# RTD_interface.net
KiCad netlist of a schematic drawn in Altium Designer
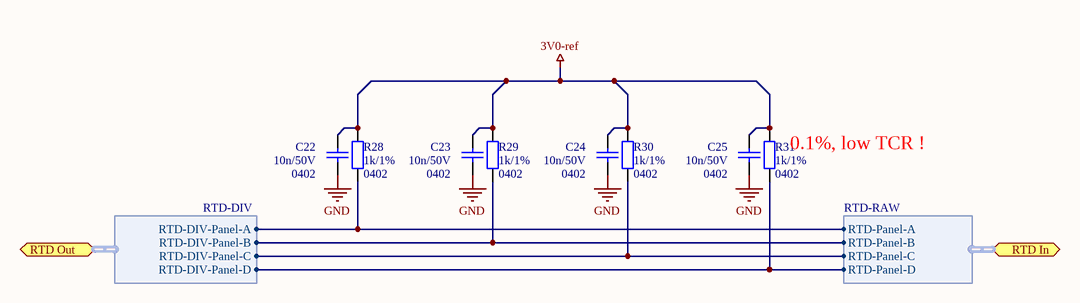
[diagram p0: RTD_interface.SchDoc]

(export (version "E")
  (design (tool "Eeschema 10.0.6"))
  (components
    (comp (ref "C22")
      (value "10n/50V")
      (footprint "SMD_Capacitor_0402")
      (description "Ceramic Cap Kemet COTS 10n/50V X7R 0402")
      (fields
        (field (name "MANUFACTURERPARTNUMBER") "C0402T103K5RALTU")
        (field (name "MANUFACTURER") "Kemet")
        (field (name "PACKAGE") "0402")
      )
      (libsource (lib "capacitors") (part "Cer_C0402T103K5RALTU"))
    )
    (comp (ref "C23")
      (value "10n/50V")
      (footprint "SMD_Capacitor_0402")
      (description "Ceramic Cap Kemet COTS 10n/50V X7R 0402")
      (fields
        (field (name "MANUFACTURERPARTNUMBER") "C0402T103K5RALTU")
        (field (name "MANUFACTURER") "Kemet")
        (field (name "PACKAGE") "0402")
      )
      (libsource (lib "capacitors") (part "Cer_C0402T103K5RALTU"))
    )
    (comp (ref "C24")
      (value "10n/50V")
      (footprint "SMD_Capacitor_0402")
      (description "Ceramic Cap Kemet COTS 10n/50V X7R 0402")
      (fields
        (field (name "MANUFACTURERPARTNUMBER") "C0402T103K5RALTU")
        (field (name "MANUFACTURER") "Kemet")
        (field (name "PACKAGE") "0402")
      )
      (libsource (lib "capacitors") (part "Cer_C0402T103K5RALTU"))
    )
    (comp (ref "C25")
      (value "10n/50V")
      (footprint "SMD_Capacitor_0402")
      (description "Ceramic Cap Kemet COTS 10n/50V X7R 0402")
      (fields
        (field (name "MANUFACTURERPARTNUMBER") "C0402T103K5RALTU")
        (field (name "MANUFACTURER") "Kemet")
        (field (name "PACKAGE") "0402")
      )
      (libsource (lib "capacitors") (part "Cer_C0402T103K5RALTU"))
    )
    (comp (ref "R28")
      (value "1k/1%")
      (footprint "SMD_Resistor_0402")
      (description "1k/1% Vishay CRCW 0402 Resistor. 63mW, 100ppm, 50V.")
      (fields
        (field (name "MANUFACTURER") "Vishay")
        (field (name "MANUFACTURERPARTNUMBER") "CRCW04021K00FKxxxx")
        (field (name "PACKAGE") "0402")
      )
      (libsource (lib "resistors") (part "CRCW04021K00FKxxxx"))
    )
    (comp (ref "R29")
      (value "1k/1%")
      (footprint "SMD_Resistor_0402")
      (description "1k/1% Vishay CRCW 0402 Resistor. 63mW, 100ppm, 50V.")
      (fields
        (field (name "MANUFACTURER") "Vishay")
        (field (name "MANUFACTURERPARTNUMBER") "CRCW04021K00FKxxxx")
        (field (name "PACKAGE") "0402")
      )
      (libsource (lib "resistors") (part "CRCW04021K00FKxxxx"))
    )
    (comp (ref "R30")
      (value "1k/1%")
      (footprint "SMD_Resistor_0402")
      (description "1k/1% Vishay CRCW 0402 Resistor. 63mW, 100ppm, 50V.")
      (fields
        (field (name "MANUFACTURER") "Vishay")
        (field (name "MANUFACTURERPARTNUMBER") "CRCW04021K00FKxxxx")
        (field (name "PACKAGE") "0402")
      )
      (libsource (lib "resistors") (part "CRCW04021K00FKxxxx"))
    )
    (comp (ref "R31")
      (value "1k/1%")
      (footprint "SMD_Resistor_0402")
      (description "1k/1% Vishay CRCW 0402 Resistor. 63mW, 100ppm, 50V.")
      (fields
        (field (name "MANUFACTURER") "Vishay")
        (field (name "MANUFACTURERPARTNUMBER") "CRCW04021K00FKxxxx")
        (field (name "PACKAGE") "0402")
      )
      (libsource (lib "resistors") (part "CRCW04021K00FKxxxx"))
    )
  )
  (nets
    (net (code "3") (name "/RTD-DIV-Panel-A") (class "Default")
      (node (ref "R28") (pin "2") (pinfunction "2_2") (pintype "passive"))
    )
    (net (code "4") (name "/RTD-DIV-Panel-B") (class "Default")
      (node (ref "R29") (pin "2") (pinfunction "2_2") (pintype "passive"))
    )
    (net (code "5") (name "/RTD-DIV-Panel-C") (class "Default")
      (node (ref "R30") (pin "2") (pinfunction "2_2") (pintype "passive"))
    )
    (net (code "6") (name "/RTD-DIV-Panel-D") (class "Default")
      (node (ref "R31") (pin "2") (pinfunction "2_2") (pintype "passive"))
    )
    (net (code "9") (name "3V0-ref") (class "Default")
      (node (ref "C22") (pin "1") (pinfunction "1_1") (pintype "passive"))
      (node (ref "C23") (pin "1") (pinfunction "1_1") (pintype "passive"))
      (node (ref "C24") (pin "1") (pinfunction "1_1") (pintype "passive"))
      (node (ref "C25") (pin "1") (pinfunction "1_1") (pintype "passive"))
      (node (ref "R28") (pin "1") (pinfunction "1_1") (pintype "passive"))
      (node (ref "R29") (pin "1") (pinfunction "1_1") (pintype "passive"))
      (node (ref "R30") (pin "1") (pinfunction "1_1") (pintype "passive"))
      (node (ref "R31") (pin "1") (pinfunction "1_1") (pintype "passive"))
    )
    (net (code "10") (name "GND") (class "Default")
      (node (ref "C22") (pin "2") (pinfunction "2_2") (pintype "passive"))
      (node (ref "C23") (pin "2") (pinfunction "2_2") (pintype "passive"))
      (node (ref "C24") (pin "2") (pinfunction "2_2") (pintype "passive"))
      (node (ref "C25") (pin "2") (pinfunction "2_2") (pintype "passive"))
    )
  )
)
